# 2_iip_rbf.net
KiCad netlist of a schematic drawn in Altium Designer
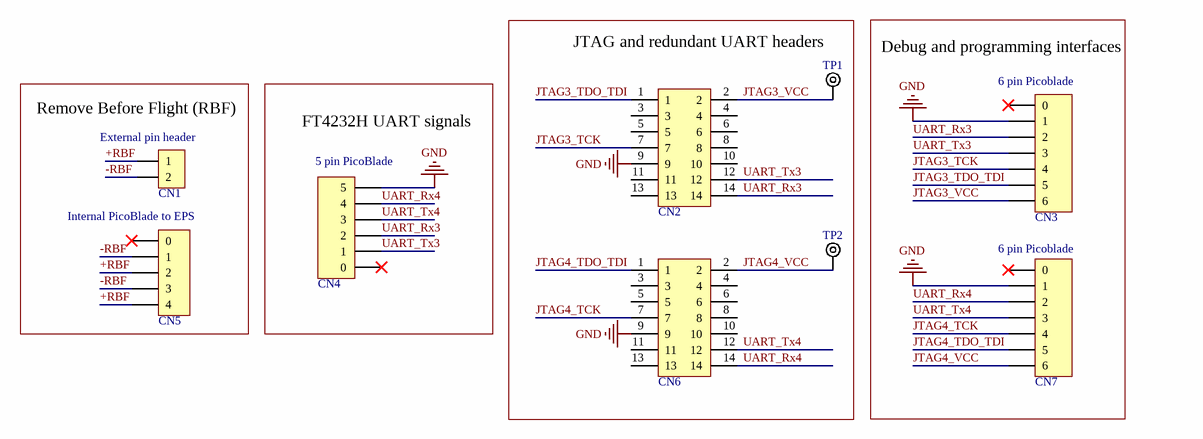
[diagram p0: 2_iip_rbf.SchDoc]

(export (version "E")
  (design (tool "Eeschema 10.0.6"))
  (components
    (comp (ref "CN1")
      (value "2 POS Pin Header")
      (footprint "CONN HEADER VERT 2POS 2.54mm")
      (description "M20 HDR, PIN, SIL, VERT, 2W")
      (fields (field (name "MANUFACTURER") "Harwin") (field (name "VOLTAGE") "50V"))
      (libsource (lib "IB_floripasat2") (part "M20-9990245"))
    )
    (comp (ref "CN2")
      (value "7 POS dual line Pin Header 2.54mm")
      (footprint "CONN HEADER VERT 14POS 2.54MM")
      (description "Headers & Wire Housings 07+07 DIL VERTICAL PIN HEADER GOLD HT")
      (fields (field (name "MANUFACTURER") "Harwin") (field (name "MANUFACTURER PART NUMBER") "M20-9980745"))
      (libsource (lib "IB_floripasat2") (part "M20-9980745"))
    )
    (comp (ref "CN3")
      (value "6 pin Picoblade")
      (footprint "PICO BLADE 0533980671")
      (description "1.25mm Pitch PicoBlade™ Header, Surface Mount, Vertical, 6 Circuits")
      (fields (field (name "MANUFACTURER") "Molex") (field (name "MANUFACTURER PART NUMBER") "53398-0671"))
      (libsource (lib "IB_floripasat2") (part "53398-0671"))
    )
    (comp (ref "CN4")
      (value "5 pin PicoBlade")
      (footprint "PICO BLADE 0533980571")
      (description "Wire-To-Board Connector, Vertical, PicoBlade 53398 Series, Surface Mount, Header, 5, 1.25 mm")
      (fields (field (name "MANUFACTURER") "Molex") (field (name "MANUFACTURER PART NUMBER") "53398-0571"))
      (libsource (lib "IB_floripasat2") (part "53398-0571"))
    )
    (comp (ref "CN5")
      (value "4 pin Picoblade")
      (footprint "PICO BLADE 0533980471")
      (description "Connector Header Surface Mount 4 position 0.049\" (1.25mm)")
      (fields (field (name "MANUFACTURER") "Molex") (field (name "MANUFACTURER PART NUMBER") "53398-0471"))
      (libsource (lib "IB_floripasat2") (part "0533980471"))
    )
    (comp (ref "CN6")
      (value "7 POS dual line Pin Header 2.54mm")
      (footprint "CONN HEADER VERT 14POS 2.54MM")
      (description "Headers & Wire Housings 07+07 DIL VERTICAL PIN HEADER GOLD HT")
      (fields (field (name "MANUFACTURER") "Harwin") (field (name "MANUFACTURER PART NUMBER") "M20-9980745"))
      (libsource (lib "IB_floripasat2") (part "M20-9980745"))
    )
    (comp (ref "CN7")
      (value "6 pin Picoblade")
      (footprint "PICO BLADE 0533980671")
      (description "1.25mm Pitch PicoBlade™ Header, Surface Mount, Vertical, 6 Circuits")
      (fields (field (name "MANUFACTURER") "Molex") (field (name "MANUFACTURER PART NUMBER") "53398-0671"))
      (libsource (lib "IB_floripasat2") (part "53398-0671"))
    )
    (comp (ref "TP1")
      (value "DNP")
      (footprint "TEST POINT PTH")
      (description "TEST POINT PAD")
      (libsource (lib "IB_floripasat2") (part "Test Point PTH"))
    )
    (comp (ref "TP2")
      (value "DNP")
      (footprint "TEST POINT PTH")
      (description "TEST POINT PAD")
      (libsource (lib "IB_floripasat2") (part "Test Point PTH"))
    )
  )
  (nets
    (net (code "1") (name "/+RBF") (class "Default")
      (node (ref "CN1") (pin "1") (pinfunction "1_1") (pintype "passive"))
      (node (ref "CN5") (pin "2") (pinfunction "2_2") (pintype "passive"))
      (node (ref "CN5") (pin "4") (pinfunction "4_4") (pintype "passive"))
    )
    (net (code "2") (name "/-RBF") (class "Default")
      (node (ref "CN1") (pin "2") (pinfunction "2_2") (pintype "passive"))
      (node (ref "CN5") (pin "1") (pinfunction "1_1") (pintype "passive"))
      (node (ref "CN5") (pin "3") (pinfunction "3_3") (pintype "passive"))
    )
    (net (code "3") (name "/JTAG3_TCK") (class "Default")
      (node (ref "CN2") (pin "7") (pinfunction "7_7") (pintype "passive"))
      (node (ref "CN3") (pin "4") (pinfunction "4_4") (pintype "passive"))
    )
    (net (code "4") (name "/JTAG3_TDO_TDI") (class "Default")
      (node (ref "CN2") (pin "1") (pinfunction "1_1") (pintype "passive"))
      (node (ref "CN3") (pin "5") (pinfunction "5_5") (pintype "passive"))
    )
    (net (code "5") (name "/JTAG3_VCC") (class "Default")
      (node (ref "CN2") (pin "2") (pinfunction "2_2") (pintype "passive"))
      (node (ref "CN3") (pin "6") (pinfunction "6_6") (pintype "passive"))
      (node (ref "TP1") (pin "1") (pinfunction "1_1") (pintype "passive"))
    )
    (net (code "6") (name "/JTAG4_TCK") (class "Default")
      (node (ref "CN6") (pin "7") (pinfunction "7_7") (pintype "passive"))
      (node (ref "CN7") (pin "4") (pinfunction "4_4") (pintype "passive"))
    )
    (net (code "7") (name "/JTAG4_TDO_TDI") (class "Default")
      (node (ref "CN6") (pin "1") (pinfunction "1_1") (pintype "passive"))
      (node (ref "CN7") (pin "5") (pinfunction "5_5") (pintype "passive"))
    )
    (net (code "8") (name "/JTAG4_VCC") (class "Default")
      (node (ref "CN6") (pin "2") (pinfunction "2_2") (pintype "passive"))
      (node (ref "CN7") (pin "6") (pinfunction "6_6") (pintype "passive"))
      (node (ref "TP2") (pin "1") (pinfunction "1_1") (pintype "passive"))
    )
    (net (code "9") (name "/UART_Rx3") (class "Default")
      (node (ref "CN2") (pin "14") (pinfunction "14_14") (pintype "passive"))
      (node (ref "CN3") (pin "2") (pinfunction "2_2") (pintype "passive"))
      (node (ref "CN4") (pin "2") (pinfunction "2_2") (pintype "passive"))
    )
    (net (code "10") (name "/UART_Rx4") (class "Default")
      (node (ref "CN4") (pin "4") (pinfunction "4_4") (pintype "passive"))
      (node (ref "CN6") (pin "14") (pinfunction "14_14") (pintype "passive"))
      (node (ref "CN7") (pin "2") (pinfunction "2_2") (pintype "passive"))
    )
    (net (code "11") (name "/UART_Tx3") (class "Default")
      (node (ref "CN2") (pin "12") (pinfunction "12_12") (pintype "passive"))
      (node (ref "CN3") (pin "3") (pinfunction "3_3") (pintype "passive"))
      (node (ref "CN4") (pin "1") (pinfunction "1_1") (pintype "passive"))
    )
    (net (code "12") (name "/UART_Tx4") (class "Default")
      (node (ref "CN4") (pin "3") (pinfunction "3_3") (pintype "passive"))
      (node (ref "CN6") (pin "12") (pinfunction "12_12") (pintype "passive"))
      (node (ref "CN7") (pin "3") (pinfunction "3_3") (pintype "passive"))
    )
    (net (code "13") (name "GND") (class "Default")
      (node (ref "CN2") (pin "9") (pinfunction "9_9") (pintype "passive"))
      (node (ref "CN3") (pin "1") (pinfunction "1_1") (pintype "passive"))
      (node (ref "CN4") (pin "5") (pinfunction "5_5") (pintype "passive"))
      (node (ref "CN6") (pin "9") (pinfunction "9_9") (pintype "passive"))
      (node (ref "CN7") (pin "1") (pinfunction "1_1") (pintype "passive"))
    )
    (net (code "14") (name "unconnected-(CN2-Pad3)") (class "Default")
      (node (ref "CN2") (pin "3") (pinfunction "3_3") (pintype "passive"))
    )
    (net (code "15") (name "unconnected-(CN2-Pad4)") (class "Default")
      (node (ref "CN2") (pin "4") (pinfunction "4_4") (pintype "passive"))
    )
    (net (code "16") (name "unconnected-(CN2-Pad5)") (class "Default")
      (node (ref "CN2") (pin "5") (pinfunction "5_5") (pintype "passive"))
    )
    (net (code "17") (name "unconnected-(CN2-Pad6)") (class "Default")
      (node (ref "CN2") (pin "6") (pinfunction "6_6") (pintype "passive"))
    )
    (net (code "18") (name "unconnected-(CN2-Pad8)") (class "Default")
      (node (ref "CN2") (pin "8") (pinfunction "8_8") (pintype "passive"))
    )
    (net (code "19") (name "unconnected-(CN2-Pad10)") (class "Default")
      (node (ref "CN2") (pin "10") (pinfunction "10_10") (pintype "passive"))
    )
    (net (code "20") (name "unconnected-(CN2-Pad11)") (class "Default")
      (node (ref "CN2") (pin "11") (pinfunction "11_11") (pintype "passive"))
    )
    (net (code "21") (name "unconnected-(CN2-Pad13)") (class "Default")
      (node (ref "CN2") (pin "13") (pinfunction "13_13") (pintype "passive"))
    )
    (net (code "22") (name "unconnected-(CN3-Pad0)") (class "Default")
      (node (ref "CN3") (pin "0") (pinfunction "0_0") (pintype "passive+no_connect"))
    )
    (net (code "23") (name "unconnected-(CN4-Pad0)") (class "Default")
      (node (ref "CN4") (pin "0") (pinfunction "0_0") (pintype "passive+no_connect"))
    )
    (net (code "24") (name "unconnected-(CN5-Pad0)") (class "Default")
      (node (ref "CN5") (pin "0") (pinfunction "0_0") (pintype "passive+no_connect"))
    )
    (net (code "25") (name "unconnected-(CN6-Pad3)") (class "Default")
      (node (ref "CN6") (pin "3") (pinfunction "3_3") (pintype "passive"))
    )
    (net (code "26") (name "unconnected-(CN6-Pad4)") (class "Default")
      (node (ref "CN6") (pin "4") (pinfunction "4_4") (pintype "passive"))
    )
    (net (code "27") (name "unconnected-(CN6-Pad5)") (class "Default")
      (node (ref "CN6") (pin "5") (pinfunction "5_5") (pintype "passive"))
    )
    (net (code "28") (name "unconnected-(CN6-Pad6)") (class "Default")
      (node (ref "CN6") (pin "6") (pinfunction "6_6") (pintype "passive"))
    )
    (net (code "29") (name "unconnected-(CN6-Pad8)") (class "Default")
      (node (ref "CN6") (pin "8") (pinfunction "8_8") (pintype "passive"))
    )
    (net (code "30") (name "unconnected-(CN6-Pad10)") (class "Default")
      (node (ref "CN6") (pin "10") (pinfunction "10_10") (pintype "passive"))
    )
    (net (code "31") (name "unconnected-(CN6-Pad11)") (class "Default")
      (node (ref "CN6") (pin "11") (pinfunction "11_11") (pintype "passive"))
    )
    (net (code "32") (name "unconnected-(CN6-Pad13)") (class "Default")
      (node (ref "CN6") (pin "13") (pinfunction "13_13") (pintype "passive"))
    )
    (net (code "33") (name "unconnected-(CN7-Pad0)") (class "Default")
      (node (ref "CN7") (pin "0") (pinfunction "0_0") (pintype "passive+no_connect"))
    )
  )
)
